# TT1-1-Top.net
KiCad netlist of a schematic drawn in Altium Designer
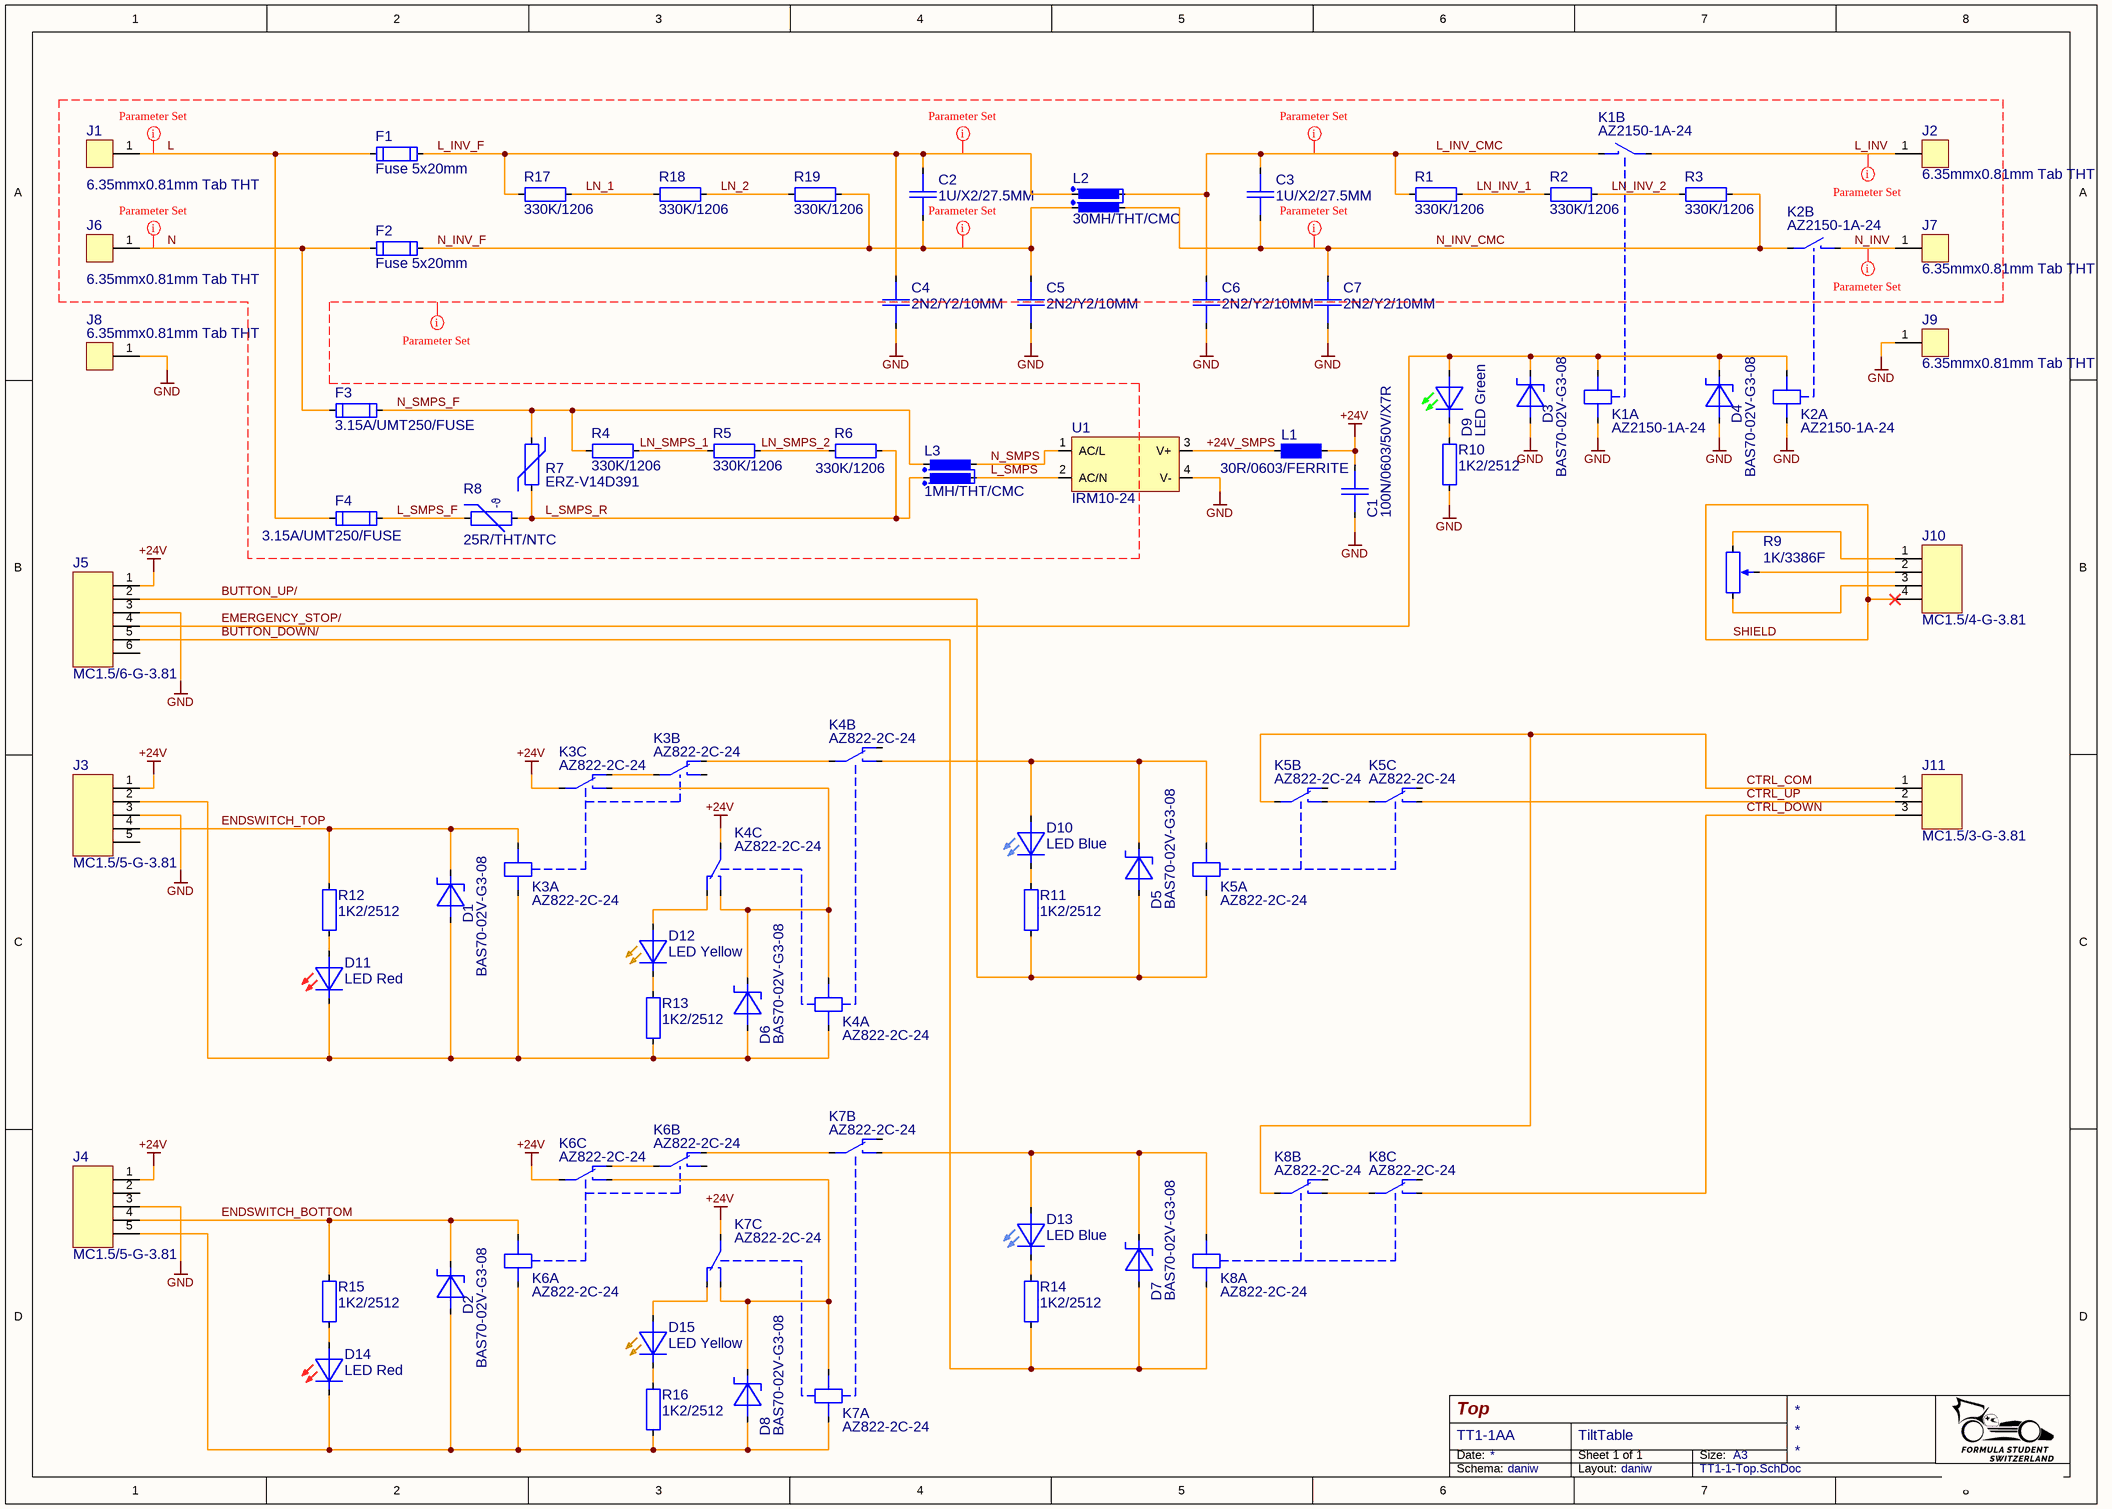
[diagram p0: TT1-1-Top.SchDoc]

(export (version "E")
  (design (tool "Eeschema 10.0.6"))
  (components
    (comp (ref "C1")
      (value "100N/0603/50V/X7R")
      (footprint "CAP0603_X7R")
      (description "CAP SM 0603 100nF 50V X7R")
      (fields (field (name "MANUFACTURER") "GENERIC"))
      (libsource (lib "daniw_altium_lib") (part "C"))
    )
    (comp (ref "C2")
      (value "1U/X2/27.5MM")
      (footprint "CAP2750P315X110X190-BL")
      (description "CAP THT 31.5X11X19 1uF 305V X2")
      (fields (field (name "MANUFACTURER") "GENERIC"))
      (libsource (lib "daniw_altium_lib") (part "C"))
    )
    (comp (ref "C3")
      (value "1U/X2/27.5MM")
      (footprint "CAP2750P315X110X190-BL")
      (description "CAP THT 31.5X11X19 1uF 305V X2")
      (fields (field (name "MANUFACTURER") "GENERIC"))
      (libsource (lib "daniw_altium_lib") (part "C"))
    )
    (comp (ref "C4")
      (value "2N2/Y2/10MM")
      (footprint "CAP1000P130X40X90-BL")
      (description "CAP THT 13X4X9 2.2nF 300V Y2")
      (fields (field (name "MANUFACTURER") "GENERIC"))
      (libsource (lib "daniw_altium_lib") (part "C"))
    )
    (comp (ref "C5")
      (value "2N2/Y2/10MM")
      (footprint "CAP1000P130X40X90-BL")
      (description "CAP THT 13X4X9 2.2nF 300V Y2")
      (fields (field (name "MANUFACTURER") "GENERIC"))
      (libsource (lib "daniw_altium_lib") (part "C"))
    )
    (comp (ref "C6")
      (value "2N2/Y2/10MM")
      (footprint "CAP1000P130X40X90-BL")
      (description "CAP THT 13X4X9 2.2nF 300V Y2")
      (fields (field (name "MANUFACTURER") "GENERIC"))
      (libsource (lib "daniw_altium_lib") (part "C"))
    )
    (comp (ref "C7")
      (value "2N2/Y2/10MM")
      (footprint "CAP1000P130X40X90-BL")
      (description "CAP THT 13X4X9 2.2nF 300V Y2")
      (fields (field (name "MANUFACTURER") "GENERIC"))
      (libsource (lib "daniw_altium_lib") (part "C"))
    )
    (comp (ref "D1")
      (value "BAS70-02V-G3-08")
      (footprint "SOD1608X065")
      (description "Small Signal Schottky Diode")
      (fields (field (name "MANUFACTURER") "Vishay"))
      (libsource (lib "daniw_altium_lib") (part "D_Schottky"))
    )
    (comp (ref "D2")
      (value "BAS70-02V-G3-08")
      (footprint "SOD1608X065")
      (description "Small Signal Schottky Diode")
      (fields (field (name "MANUFACTURER") "Vishay"))
      (libsource (lib "daniw_altium_lib") (part "D_Schottky"))
    )
    (comp (ref "D3")
      (value "BAS70-02V-G3-08")
      (footprint "SOD1608X065")
      (description "Small Signal Schottky Diode")
      (fields (field (name "MANUFACTURER") "Vishay"))
      (libsource (lib "daniw_altium_lib") (part "D_Schottky"))
    )
    (comp (ref "D4")
      (value "BAS70-02V-G3-08")
      (footprint "SOD1608X065")
      (description "Small Signal Schottky Diode")
      (fields (field (name "MANUFACTURER") "Vishay"))
      (libsource (lib "daniw_altium_lib") (part "D_Schottky"))
    )
    (comp (ref "D5")
      (value "BAS70-02V-G3-08")
      (footprint "SOD1608X065")
      (description "Small Signal Schottky Diode")
      (fields (field (name "MANUFACTURER") "Vishay"))
      (libsource (lib "daniw_altium_lib") (part "D_Schottky"))
    )
    (comp (ref "D6")
      (value "BAS70-02V-G3-08")
      (footprint "SOD1608X065")
      (description "Small Signal Schottky Diode")
      (fields (field (name "MANUFACTURER") "Vishay"))
      (libsource (lib "daniw_altium_lib") (part "D_Schottky"))
    )
    (comp (ref "D7")
      (value "BAS70-02V-G3-08")
      (footprint "SOD1608X065")
      (description "Small Signal Schottky Diode")
      (fields (field (name "MANUFACTURER") "Vishay"))
      (libsource (lib "daniw_altium_lib") (part "D_Schottky"))
    )
    (comp (ref "D8")
      (value "BAS70-02V-G3-08")
      (footprint "SOD1608X065")
      (description "Small Signal Schottky Diode")
      (fields (field (name "MANUFACTURER") "Vishay"))
      (libsource (lib "daniw_altium_lib") (part "D_Schottky"))
    )
    (comp (ref "D9")
      (value "LED Green")
      (footprint "LED0603_GREEN")
      (description "Generic LED Green 0603")
      (fields (field (name "PART NUMBER") "LED Green 0603") (field (name "MANUFACTURER") "GENERIC"))
      (libsource (lib "daniw_altium_lib") (part "LED_GREEN"))
    )
    (comp (ref "D10")
      (value "LED Blue")
      (footprint "LED0603_BLUE")
      (description "Generic LED Blue 0603")
      (fields (field (name "PART NUMBER") "LED Blue 0603") (field (name "MANUFACTURER") "GENERIC"))
      (libsource (lib "daniw_altium_lib") (part "LED_BLUE"))
    )
    (comp (ref "D11")
      (value "LED Red")
      (footprint "LED0603_RED")
      (description "Generic LED Red 0603")
      (fields (field (name "PART NUMBER") "LED Red 0603") (field (name "MANUFACTURER") "GENERIC"))
      (libsource (lib "daniw_altium_lib") (part "LED_RED"))
    )
    (comp (ref "D12")
      (value "LED Yellow")
      (footprint "LED0603_YELLOW")
      (description "Generic LED Yellow 0603")
      (fields (field (name "PART NUMBER") "LED Yellow 0603") (field (name "MANUFACTURER") "GENERIC"))
      (libsource (lib "daniw_altium_lib") (part "LED_YELLOW"))
    )
    (comp (ref "D13")
      (value "LED Blue")
      (footprint "LED0603_BLUE")
      (description "Generic LED Blue 0603")
      (fields (field (name "PART NUMBER") "LED Blue 0603") (field (name "MANUFACTURER") "GENERIC"))
      (libsource (lib "daniw_altium_lib") (part "LED_BLUE"))
    )
    (comp (ref "D14")
      (value "LED Red")
      (footprint "LED0603_RED")
      (description "Generic LED Red 0603")
      (fields (field (name "PART NUMBER") "LED Red 0603") (field (name "MANUFACTURER") "GENERIC"))
      (libsource (lib "daniw_altium_lib") (part "LED_RED"))
    )
    (comp (ref "D15")
      (value "LED Yellow")
      (footprint "LED0603_YELLOW")
      (description "Generic LED Yellow 0603")
      (fields (field (name "PART NUMBER") "LED Yellow 0603") (field (name "MANUFACTURER") "GENERIC"))
      (libsource (lib "daniw_altium_lib") (part "LED_YELLOW"))
    )
    (comp (ref "F1")
      (value "Fuse 5x20mm")
      (footprint "OGN_THR")
      (description "open fuse holder, 5 x 20 mm, THR, IEC 60335-1")
      (fields (field (name "PART NUMBER") "Fuse/5x20mm/OGN") (field (name "MANUFACTURER") "Schurter"))
      (libsource (lib "daniw_altium_lib") (part "Fuse"))
    )
    (comp (ref "F2")
      (value "Fuse 5x20mm")
      (footprint "OGN_THR")
      (description "open fuse holder, 5 x 20 mm, THR, IEC 60335-1")
      (fields (field (name "PART NUMBER") "Fuse/5x20mm/OGN") (field (name "MANUFACTURER") "Schurter"))
      (libsource (lib "daniw_altium_lib") (part "Fuse"))
    )
    (comp (ref "F3")
      (value "3.15A/UMT250/FUSE")
      (footprint "UMT250")
      (description "Fuse 250VAC 3.15A UMT250")
      (fields (field (name "MANUFACTURER") "Schurter"))
      (libsource (lib "daniw_altium_lib") (part "Fuse"))
    )
    (comp (ref "F4")
      (value "3.15A/UMT250/FUSE")
      (footprint "UMT250")
      (description "Fuse 250VAC 3.15A UMT250")
      (fields (field (name "MANUFACTURER") "Schurter"))
      (libsource (lib "daniw_altium_lib") (part "Fuse"))
    )
    (comp (ref "J1")
      (value "6.35mmx0.81mm Tab THT")
      (footprint "Tab_THT_635")
      (description "CONN QC TAB 0.250 SOLDER")
      (fields (field (name "PART NUMBER") "Tab_025_THT") (field (name "MANUFACTURER") "GENERIC"))
      (libsource (lib "") (part "CON1_1"))
    )
    (comp (ref "J2")
      (value "6.35mmx0.81mm Tab THT")
      (footprint "Tab_THT_635")
      (description "CONN QC TAB 0.250 SOLDER")
      (fields (field (name "PART NUMBER") "Tab_025_THT") (field (name "MANUFACTURER") "GENERIC"))
      (libsource (lib "daniw_altium_lib") (part "CON1"))
    )
    (comp (ref "J3")
      (value "MC1.5/5-G-3.81")
      (footprint "MC1.5/5-G-3.81")
      (description "Phoenix contact MC 1,5/ 5-G-3,81")
      (fields (field (name "MANUFACTURER") "Phoenix"))
      (libsource (lib "daniw_altium_lib") (part "CON5"))
    )
    (comp (ref "J4")
      (value "MC1.5/5-G-3.81")
      (footprint "MC1.5/5-G-3.81")
      (description "Phoenix contact MC 1,5/ 5-G-3,81")
      (fields (field (name "MANUFACTURER") "Phoenix"))
      (libsource (lib "daniw_altium_lib") (part "CON5"))
    )
    (comp (ref "J5")
      (value "MC1.5/6-G-3.81")
      (footprint "MC1.5/6-G-3.81")
      (description "Phoenix contact MC 1,5/ 6-G-3,81")
      (fields (field (name "MANUFACTURER") "Phoenix"))
      (libsource (lib "daniw_altium_lib") (part "CON6"))
    )
    (comp (ref "J6")
      (value "6.35mmx0.81mm Tab THT")
      (footprint "Tab_THT_635")
      (description "CONN QC TAB 0.250 SOLDER")
      (fields (field (name "PART NUMBER") "Tab_025_THT") (field (name "MANUFACTURER") "GENERIC"))
      (libsource (lib "") (part "CON1_1"))
    )
    (comp (ref "J7")
      (value "6.35mmx0.81mm Tab THT")
      (footprint "Tab_THT_635")
      (description "CONN QC TAB 0.250 SOLDER")
      (fields (field (name "PART NUMBER") "Tab_025_THT") (field (name "MANUFACTURER") "GENERIC"))
      (libsource (lib "daniw_altium_lib") (part "CON1"))
    )
    (comp (ref "J8")
      (value "6.35mmx0.81mm Tab THT")
      (footprint "Tab_THT_635")
      (description "CONN QC TAB 0.250 SOLDER")
      (fields (field (name "PART NUMBER") "Tab_025_THT") (field (name "MANUFACTURER") "GENERIC"))
      (libsource (lib "") (part "CON1_1"))
    )
    (comp (ref "J9")
      (value "6.35mmx0.81mm Tab THT")
      (footprint "Tab_THT_635")
      (description "CONN QC TAB 0.250 SOLDER")
      (fields (field (name "PART NUMBER") "Tab_025_THT") (field (name "MANUFACTURER") "GENERIC"))
      (libsource (lib "daniw_altium_lib") (part "CON1"))
    )
    (comp (ref "J10")
      (value "MC1.5/4-G-3.81")
      (footprint "MC1.5/4-G-3.81")
      (description "Phoenix contact MC 1,5/ 4-G-3,81")
      (fields (field (name "MANUFACTURER") "Phoenix"))
      (libsource (lib "daniw_altium_lib") (part "CON4"))
    )
    (comp (ref "J11")
      (value "MC1.5/3-G-3.81")
      (footprint "MC1.5/3-G-3.81")
      (description "Phoenix contact MC 1,5/ 3-G-3,81")
      (fields (field (name "MANUFACTURER") "Phoenix"))
      (libsource (lib "daniw_altium_lib") (part "CON3"))
    )
    (comp (ref "K1")
      (value "AZ2150-1A-24")
      (footprint "AZ2150-SPST-NO")
      (description "Miniature Power Relay, SPST-NO, 24V Coil, 40A 30VDC 300VAC")
      (fields (field (name "MANUFACTURER") "Zettler"))
      (libsource (lib "daniw_altium_lib") (part "REL_SPST_NO"))
    )
    (comp (ref "K2")
      (value "AZ2150-1A-24")
      (footprint "AZ2150-SPST-NO")
      (description "Miniature Power Relay, SPST-NO, 24V Coil, 40A 30VDC 300VAC")
      (fields (field (name "MANUFACTURER") "Zettler"))
      (libsource (lib "daniw_altium_lib") (part "REL_SPST_NO"))
    )
    (comp (ref "K3")
      (value "AZ822-2C-24")
      (footprint "AZ822")
      (description "Subminiature DIP Relay, DPDT, 24V 98mW Coil, 2A 220VDC 250VAC")
      (fields (field (name "MANUFACTURER") "Zettler"))
      (libsource (lib "daniw_altium_lib") (part "REL_DPDT"))
    )
    (comp (ref "K4")
      (value "AZ822-2C-24")
      (footprint "AZ822")
      (description "Subminiature DIP Relay, DPDT, 24V 98mW Coil, 2A 220VDC 250VAC")
      (fields (field (name "MANUFACTURER") "Zettler"))
      (libsource (lib "daniw_altium_lib") (part "REL_DPDT"))
    )
    (comp (ref "K5")
      (value "AZ822-2C-24")
      (footprint "AZ822")
      (description "Subminiature DIP Relay, DPDT, 24V 98mW Coil, 2A 220VDC 250VAC")
      (fields (field (name "MANUFACTURER") "Zettler"))
      (libsource (lib "daniw_altium_lib") (part "REL_DPDT"))
    )
    (comp (ref "K6")
      (value "AZ822-2C-24")
      (footprint "AZ822")
      (description "Subminiature DIP Relay, DPDT, 24V 98mW Coil, 2A 220VDC 250VAC")
      (fields (field (name "MANUFACTURER") "Zettler"))
      (libsource (lib "daniw_altium_lib") (part "REL_DPDT"))
    )
    (comp (ref "K7")
      (value "AZ822-2C-24")
      (footprint "AZ822")
      (description "Subminiature DIP Relay, DPDT, 24V 98mW Coil, 2A 220VDC 250VAC")
      (fields (field (name "MANUFACTURER") "Zettler"))
      (libsource (lib "daniw_altium_lib") (part "REL_DPDT"))
    )
    (comp (ref "K8")
      (value "AZ822-2C-24")
      (footprint "AZ822")
      (description "Subminiature DIP Relay, DPDT, 24V 98mW Coil, 2A 220VDC 250VAC")
      (fields (field (name "MANUFACTURER") "Zettler"))
      (libsource (lib "daniw_altium_lib") (part "REL_DPDT"))
    )
    (comp (ref "L1")
      (value "30R/0603/FERRITE")
      (footprint "FB0603")
      (description "30R@100MHz 5A 0603 Ferrite")
      (fields (field (name "MANUFACTURER") "GENERIC"))
      (libsource (lib "daniw_altium_lib") (part "Ferrite"))
    )
    (comp (ref "L2")
      (value "30MH/THT/CMC")
      (footprint "CMC-WE-CMBNC-XL-7448050530")
      (description "CMC 30mH 5A Würth CMBNC 7448050530")
      (fields (field (name "MANUFACTURER") "Würth"))
      (libsource (lib "daniw_altium_lib") (part "L_CMC_2"))
    )
    (comp (ref "L3")
      (value "1MH/THT/CMC")
      (footprint "DFKH-CASE-50-2")
      (description "CMC 1mH 2A THT Schurter DFKH-14-0003")
      (fields (field (name "MANUFACTURER") "SCHURTER"))
      (libsource (lib "") (part "L_CMC_2_1"))
    )
    (comp (ref "R1")
      (value "330K/1206")
      (footprint "R1206-0.80-WW")
      (description "RES SM 1206 330K")
      (fields (field (name "MANUFACTURER") "GENERIC"))
      (libsource (lib "daniw_altium_lib") (part "R"))
    )
    (comp (ref "R2")
      (value "330K/1206")
      (footprint "R1206-0.80-WW")
      (description "RES SM 1206 330K")
      (fields (field (name "MANUFACTURER") "GENERIC"))
      (libsource (lib "daniw_altium_lib") (part "R"))
    )
    (comp (ref "R3")
      (value "330K/1206")
      (footprint "R1206-0.80-WW")
      (description "RES SM 1206 330K")
      (fields (field (name "MANUFACTURER") "GENERIC"))
      (libsource (lib "daniw_altium_lib") (part "R"))
    )
    (comp (ref "R4")
      (value "330K/1206")
      (footprint "R1206-0.80-WW")
      (description "RES SM 1206 330K")
      (fields (field (name "MANUFACTURER") "GENERIC"))
      (libsource (lib "daniw_altium_lib") (part "R"))
    )
    (comp (ref "R5")
      (value "330K/1206")
      (footprint "R1206-0.80-WW")
      (description "RES SM 1206 330K")
      (fields (field (name "MANUFACTURER") "GENERIC"))
      (libsource (lib "daniw_altium_lib") (part "R"))
    )
    (comp (ref "R6")
      (value "330K/1206")
      (footprint "R1206-0.80-WW")
      (description "RES SM 1206 330K")
      (fields (field (name "MANUFACTURER") "GENERIC"))
      (libsource (lib "daniw_altium_lib") (part "R"))
    )
    (comp (ref "R7")
      (value "ERZ-V14D391")
      (footprint "RESD750W80D155")
      (description "VARISTOR 391V 6kA")
      (fields (field (name "MANUFACTURER") "GENERIC"))
      (libsource (lib "daniw_altium_lib") (part "R_VAR"))
    )
    (comp (ref "R8")
      (value "25R/THT/NTC")
      (footprint "RESD500W60D115")
      (description "RES NTC THT 5 25R")
      (fields (field (name "MANUFACTURER") "GENERIC"))
      (libsource (lib "daniw_altium_lib") (part "R_NTC"))
    )
    (comp (ref "R9")
      (value "1K/3386F")
      (footprint "3386F")
      (description "RES POT 3386F 1K")
      (fields (field (name "MANUFACTURER") "Bourns"))
      (libsource (lib "daniw_altium_lib") (part "R_POT"))
    )
    (comp (ref "R10")
      (value "1K2/2512")
      (footprint "R2512-0.65-WW")
      (description "RES SM 2512 1K2")
      (fields (field (name "MANUFACTURER") "GENERIC"))
      (libsource (lib "daniw_altium_lib") (part "R"))
    )
    (comp (ref "R11")
      (value "1K2/2512")
      (footprint "R2512-0.65-WW")
      (description "RES SM 2512 1K2")
      (fields (field (name "MANUFACTURER") "GENERIC"))
      (libsource (lib "daniw_altium_lib") (part "R"))
    )
    (comp (ref "R12")
      (value "1K2/2512")
      (footprint "R2512-0.65-WW")
      (description "RES SM 2512 1K2")
      (fields (field (name "MANUFACTURER") "GENERIC"))
      (libsource (lib "daniw_altium_lib") (part "R"))
    )
    (comp (ref "R13")
      (value "1K2/2512")
      (footprint "R2512-0.65-WW")
      (description "RES SM 2512 1K2")
      (fields (field (name "MANUFACTURER") "GENERIC"))
      (libsource (lib "daniw_altium_lib") (part "R"))
    )
    (comp (ref "R14")
      (value "1K2/2512")
      (footprint "R2512-0.65-WW")
      (description "RES SM 2512 1K2")
      (fields (field (name "MANUFACTURER") "GENERIC"))
      (libsource (lib "daniw_altium_lib") (part "R"))
    )
    (comp (ref "R15")
      (value "1K2/2512")
      (footprint "R2512-0.65-WW")
      (description "RES SM 2512 1K2")
      (fields (field (name "MANUFACTURER") "GENERIC"))
      (libsource (lib "daniw_altium_lib") (part "R"))
    )
    (comp (ref "R16")
      (value "1K2/2512")
      (footprint "R2512-0.65-WW")
      (description "RES SM 2512 1K2")
      (fields (field (name "MANUFACTURER") "GENERIC"))
      (libsource (lib "daniw_altium_lib") (part "R"))
    )
    (comp (ref "R17")
      (value "330K/1206")
      (footprint "R1206-0.80-WW")
      (description "RES SM 1206 330K")
      (fields (field (name "MANUFACTURER") "GENERIC"))
      (libsource (lib "daniw_altium_lib") (part "R"))
    )
    (comp (ref "R18")
      (value "330K/1206")
      (footprint "R1206-0.80-WW")
      (description "RES SM 1206 330K")
      (fields (field (name "MANUFACTURER") "GENERIC"))
      (libsource (lib "daniw_altium_lib") (part "R"))
    )
    (comp (ref "R19")
      (value "330K/1206")
      (footprint "R1206-0.80-WW")
      (description "RES SM 1206 330K")
      (fields (field (name "MANUFACTURER") "GENERIC"))
      (libsource (lib "daniw_altium_lib") (part "R"))
    )
    (comp (ref "U1")
      (value "IRM10-24")
      (footprint "IRM10")
      (description "10W AC-DC PCB-Mount Green Power Module, 24V")
      (libsource (lib "daniw_altium_lib") (part "IRM30"))
    )
  )
  (nets
    (net (code "1") (name "+24V") (class "Default")
      (node (ref "C1") (pin "1") (pinfunction "1_1") (pintype "passive"))
      (node (ref "J3") (pin "1") (pintype "passive"))
      (node (ref "J4") (pin "1") (pintype "passive"))
      (node (ref "J5") (pin "1") (pintype "passive"))
      (node (ref "K3") (pin "6") (pinfunction "COM2_6") (pintype "passive"))
      (node (ref "K4") (pin "6") (pinfunction "COM2_6") (pintype "passive"))
      (node (ref "K6") (pin "6") (pinfunction "COM2_6") (pintype "passive"))
      (node (ref "K7") (pin "6") (pinfunction "COM2_6") (pintype "passive"))
      (node (ref "L1") (pin "2") (pinfunction "2_2") (pintype "passive"))
    )
    (net (code "2") (name "/+24V_SMPS") (class "Default")
      (node (ref "L1") (pin "1") (pinfunction "1_1") (pintype "passive"))
      (node (ref "U1") (pin "3") (pinfunction "V+_3") (pintype "passive"))
    )
    (net (code "3") (name "/BUTTON_DOWN{slash}") (class "Default")
      (node (ref "D7") (pin "2") (pinfunction "2_2") (pintype "passive"))
      (node (ref "J5") (pin "5") (pintype "passive"))
      (node (ref "K8") (pin "2") (pinfunction "2_2") (pintype "passive"))
      (node (ref "R14") (pin "2") (pinfunction "2_2") (pintype "passive"))
    )
    (net (code "4") (name "/BUTTON_UP{slash}") (class "Default")
      (node (ref "D5") (pin "2") (pinfunction "2_2") (pintype "passive"))
      (node (ref "J5") (pin "2") (pintype "passive"))
      (node (ref "K5") (pin "1") (pinfunction "1_1") (pintype "passive"))
      (node (ref "R11") (pin "2") (pinfunction "2_2") (pintype "passive"))
    )
    (net (code "5") (name "/CTRL_COM") (class "Default")
      (node (ref "J11") (pin "1") (pintype "passive"))
      (node (ref "K5") (pin "3") (pinfunction "COM1_3") (pintype "passive"))
      (node (ref "K8") (pin "3") (pinfunction "COM1_3") (pintype "passive"))
    )
    (net (code "6") (name "/CTRL_DOWN") (class "Default")
      (node (ref "J11") (pin "3") (pintype "passive"))
      (node (ref "K8") (pin "8") (pinfunction "NO2_8") (pintype "passive"))
    )
    (net (code "7") (name "/CTRL_UP") (class "Default")
      (node (ref "J11") (pin "2") (pintype "passive"))
      (node (ref "K5") (pin "8") (pinfunction "NO2_8") (pintype "passive"))
    )
    (net (code "8") (name "/EMERGENCY_STOP{slash}") (class "Default")
      (node (ref "D3") (pin "1") (pinfunction "1_1") (pintype "passive"))
      (node (ref "D4") (pin "1") (pinfunction "1_1") (pintype "passive"))
      (node (ref "D9") (pin "2") (pinfunction "2_2") (pintype "passive"))
      (node (ref "J5") (pin "4") (pintype "passive"))
      (node (ref "K1") (pin "1") (pinfunction "1_1") (pintype "passive"))
      (node (ref "K2") (pin "1") (pinfunction "1_1") (pintype "passive"))
    )
    (net (code "9") (name "/ENDSWITCH_BOTTOM") (class "Default")
      (node (ref "D2") (pin "1") (pinfunction "1_1") (pintype "passive"))
      (node (ref "J4") (pin "4") (pintype "passive"))
      (node (ref "K6") (pin "1") (pinfunction "1_1") (pintype "passive"))
      (node (ref "R15") (pin "1") (pinfunction "1_1") (pintype "passive"))
    )
    (net (code "10") (name "/ENDSWITCH_TOP") (class "Default")
      (node (ref "D1") (pin "1") (pinfunction "1_1") (pintype "passive"))
      (node (ref "J3") (pin "4") (pintype "passive"))
      (node (ref "K3") (pin "1") (pinfunction "1_1") (pintype "passive"))
      (node (ref "R12") (pin "1") (pinfunction "1_1") (pintype "passive"))
    )
    (net (code "11") (name "/L") (class "Default")
      (node (ref "F1") (pin "1") (pinfunction "1_1") (pintype "passive"))
      (node (ref "F4") (pin "1") (pinfunction "1_1") (pintype "passive"))
      (node (ref "J1") (pin "1") (pintype "passive"))
    )
    (net (code "12") (name "/LN_1") (class "Default")
      (node (ref "R17") (pin "2") (pinfunction "2_2") (pintype "passive"))
      (node (ref "R18") (pin "1") (pinfunction "1_1") (pintype "passive"))
    )
    (net (code "13") (name "/LN_2") (class "Default")
      (node (ref "R18") (pin "2") (pinfunction "2_2") (pintype "passive"))
      (node (ref "R19") (pin "1") (pinfunction "1_1") (pintype "passive"))
    )
    (net (code "14") (name "/LN_INV_1") (class "Default")
      (node (ref "R1") (pin "2") (pinfunction "2_2") (pintype "passive"))
      (node (ref "R2") (pin "1") (pinfunction "1_1") (pintype "passive"))
    )
    (net (code "15") (name "/LN_INV_2") (class "Default")
      (node (ref "R2") (pin "2") (pinfunction "2_2") (pintype "passive"))
      (node (ref "R3") (pin "1") (pinfunction "1_1") (pintype "passive"))
    )
    (net (code "16") (name "/LN_SMPS_1") (class "Default")
      (node (ref "R4") (pin "2") (pinfunction "2_2") (pintype "passive"))
      (node (ref "R5") (pin "2") (pinfunction "2_2") (pintype "passive"))
    )
    (net (code "17") (name "/LN_SMPS_2") (class "Default")
      (node (ref "R5") (pin "1") (pinfunction "1_1") (pintype "passive"))
      (node (ref "R6") (pin "1") (pinfunction "1_1") (pintype "passive"))
    )
    (net (code "18") (name "/L_INV") (class "Default")
      (node (ref "J2") (pin "1") (pintype "passive"))
      (node (ref "K1") (pin "3") (pinfunction "COM1_3") (pintype "passive"))
    )
    (net (code "19") (name "/L_INV_CMC") (class "Default")
      (node (ref "C3") (pin "1") (pinfunction "1_1") (pintype "passive"))
      (node (ref "C6") (pin "1") (pinfunction "1_1") (pintype "passive"))
      (node (ref "K1") (pin "4") (pinfunction "NO1_4") (pintype "passive"))
      (node (ref "L2") (pin "4") (pinfunction "4_4") (pintype "passive"))
      (node (ref "R1") (pin "1") (pinfunction "1_1") (pintype "passive"))
    )
    (net (code "20") (name "/L_INV_F") (class "Default")
      (node (ref "C2") (pin "1") (pinfunction "1_1") (pintype "passive"))
      (node (ref "C4") (pin "1") (pinfunction "1_1") (pintype "passive"))
      (node (ref "F1") (pin "2") (pinfunction "2_2") (pintype "passive"))
      (node (ref "L2") (pin "2") (pinfunction "2_2") (pintype "passive"))
      (node (ref "R17") (pin "1") (pinfunction "1_1") (pintype "passive"))
    )
    (net (code "21") (name "/L_SMPS") (class "Default")
      (node (ref "L3") (pin "4") (pinfunction "4_4") (pintype "passive"))
      (node (ref "U1") (pin "2") (pinfunction "AC/N_2") (pintype "passive"))
    )
    (net (code "22") (name "/L_SMPS_F") (class "Default")
      (node (ref "F4") (pin "2") (pinfunction "2_2") (pintype "passive"))
      (node (ref "R8") (pin "1") (pinfunction "1_1") (pintype "passive"))
    )
    (net (code "23") (name "/L_SMPS_R") (class "Default")
      (node (ref "L3") (pin "2") (pinfunction "2_2") (pintype "passive"))
      (node (ref "R6") (pin "2") (pinfunction "2_2") (pintype "passive"))
      (node (ref "R7") (pin "2") (pinfunction "2_2") (pintype "passive"))
      (node (ref "R8") (pin "2") (pinfunction "2_2") (pintype "passive"))
    )
    (net (code "24") (name "/N") (class "Default")
      (node (ref "F2") (pin "1") (pinfunction "1_1") (pintype "passive"))
      (node (ref "F3") (pin "1") (pinfunction "1_1") (pintype "passive"))
      (node (ref "J6") (pin "1") (pintype "passive"))
    )
    (net (code "25") (name "/N_INV") (class "Default")
      (node (ref "J7") (pin "1") (pintype "passive"))
      (node (ref "K2") (pin "4") (pinfunction "NO1_4") (pintype "passive"))
    )
    (net (code "26") (name "/N_INV_CMC") (class "Default")
      (node (ref "C3") (pin "2") (pinfunction "2_2") (pintype "passive"))
      (node (ref "C7") (pin "1") (pinfunction "1_1") (pintype "passive"))
      (node (ref "K2") (pin "3") (pinfunction "COM1_3") (pintype "passive"))
      (node (ref "L2") (pin "3") (pinfunction "3_3") (pintype "passive"))
      (node (ref "R3") (pin "2") (pinfunction "2_2") (pintype "passive"))
    )
    (net (code "27") (name "/N_INV_F") (class "Default")
      (node (ref "C2") (pin "2") (pinfunction "2_2") (pintype "passive"))
      (node (ref "C5") (pin "1") (pinfunction "1_1") (pintype "passive"))
      (node (ref "F2") (pin "2") (pinfunction "2_2") (pintype "passive"))
      (node (ref "L2") (pin "1") (pinfunction "1_1") (pintype "passive"))
      (node (ref "R19") (pin "2") (pinfunction "2_2") (pintype "passive"))
    )
    (net (code "28") (name "/N_SMPS") (class "Default")
      (node (ref "L3") (pin "3") (pinfunction "3_3") (pintype "passive"))
      (node (ref "U1") (pin "1") (pinfunction "AC/L_1") (pintype "passive"))
    )
    (net (code "29") (name "/N_SMPS_F") (class "Default")
      (node (ref "F3") (pin "2") (pinfunction "2_2") (pintype "passive"))
      (node (ref "L3") (pin "1") (pinfunction "1_1") (pintype "passive"))
      (node (ref "R4") (pin "1") (pinfunction "1_1") (pintype "passive"))
      (node (ref "R7") (pin "1") (pinfunction "1_1") (pintype "passive"))
    )
    (net (code "30") (name "/SHIELD") (class "Default")
      (node (ref "J10") (pin "4") (pintype "passive+no_connect"))
    )
    (net (code "31") (name "GND") (class "Default")
      (node (ref "C1") (pin "2") (pinfunction "2_2") (pintype "passive"))
      (node (ref "C4") (pin "2") (pinfunction "2_2") (pintype "passive"))
      (node (ref "C5") (pin "2") (pinfunction "2_2") (pintype "passive"))
      (node (ref "C6") (pin "2") (pinfunction "2_2") (pintype "passive"))
      (node (ref "C7") (pin "2") (pinfunction "2_2") (pintype "passive"))
      (node (ref "D3") (pin "2") (pinfunction "2_2") (pintype "passive"))
      (node (ref "D4") (pin "2") (pinfunction "2_2") (pintype "passive"))
      (node (ref "J3") (pin "3") (pintype "passive"))
      (node (ref "J4") (pin "3") (pintype "passive"))
      (node (ref "J5") (pin "3") (pintype "passive"))
      (node (ref "J8") (pin "1") (pintype "passive"))
      (node (ref "J9") (pin "1") (pintype "passive"))
      (node (ref "K1") (pin "2") (pinfunction "2_2") (pintype "passive"))
      (node (ref "K2") (pin "2") (pinfunction "2_2") (pintype "passive"))
      (node (ref "R10") (pin "2") (pinfunction "2_2") (pintype "passive"))
      (node (ref "U1") (pin "4") (pinfunction "V-_4") (pintype "passive"))
    )
    (net (code "32") (name "Net-(D1-Pad2)") (class "Default")
      (node (ref "D1") (pin "2") (pinfunction "2_2") (pintype "passive"))
      (node (ref "D11") (pin "1") (pinfunction "1_1") (pintype "passive"))
      (node (ref "D6") (pin "2") (pinfunction "2_2") (pintype "passive"))
      (node (ref "J3") (pin "2") (pintype "passive"))
      (node (ref "K3") (pin "2") (pinfunction "2_2") (pintype "passive"))
      (node (ref "K4") (pin "2") (pinfunction "2_2") (pintype "passive"))
      (node (ref "R13") (pin "2") (pinfunction "2_2") (pintype "passive"))
    )
    (net (code "33") (name "Net-(D9-Pad1)") (class "Default")
      (node (ref "D9") (pin "1") (pinfunction "1_1") (pintype "passive"))
      (node (ref "R10") (pin "1") (pinfunction "1_1") (pintype "passive"))
    )
    (net (code "34") (name "Net-(D10-Pad1)") (class "Default")
      (node (ref "D10") (pin "1") (pinfunction "1_1") (pintype "passive"))
      (node (ref "R11") (pin "1") (pinfunction "1_1") (pintype "passive"))
    )
    (net (code "35") (name "Net-(D11-Pad2)") (class "Default")
      (node (ref "D11") (pin "2") (pinfunction "2_2") (pintype "passive"))
      (node (ref "R12") (pin "2") (pinfunction "2_2") (pintype "passive"))
    )
    (net (code "36") (name "Net-(D12-Pad1)") (class "Default")
      (node (ref "D12") (pin "1") (pinfunction "1_1") (pintype "passive"))
      (node (ref "R13") (pin "1") (pinfunction "1_1") (pintype "passive"))
    )
    (net (code "37") (name "Net-(D13-Pad1)") (class "Default")
      (node (ref "D13") (pin "1") (pinfunction "1_1") (pintype "passive"))
      (node (ref "R14") (pin "1") (pinfunction "1_1") (pintype "passive"))
    )
    (net (code "38") (name "Net-(D14-Pad1)") (class "Default")
      (node (ref "D14") (pin "1") (pinfunction "1_1") (pintype "passive"))
      (node (ref "D2") (pin "2") (pinfunction "2_2") (pintype "passive"))
      (node (ref "D8") (pin "2") (pinfunction "2_2") (pintype "passive"))
      (node (ref "J4") (pin "5") (pintype "passive"))
      (node (ref "K6") (pin "2") (pinfunction "2_2") (pintype "passive"))
      (node (ref "K7") (pin "2") (pinfunction "2_2") (pintype "passive"))
      (node (ref "R16") (pin "2") (pinfunction "2_2") (pintype "passive"))
    )
    (net (code "39") (name "Net-(D14-Pad2)") (class "Default")
      (node (ref "D14") (pin "2") (pinfunction "2_2") (pintype "passive"))
      (node (ref "R15") (pin "2") (pinfunction "2_2") (pintype "passive"))
    )
    (net (code "40") (name "Net-(D15-Pad1)") (class "Default")
      (node (ref "D15") (pin "1") (pinfunction "1_1") (pintype "passive"))
      (node (ref "R16") (pin "1") (pinfunction "1_1") (pintype "passive"))
    )
    (net (code "41") (name "Net-(J10-Pad1)") (class "Default")
      (node (ref "J10") (pin "1") (pintype "passive"))
      (node (ref "R9") (pin "2") (pinfunction "2_2") (pintype "passive"))
    )
    (net (code "42") (name "Net-(J10-Pad2)") (class "Default")
      (node (ref "J10") (pin "2") (pintype "passive"))
      (node (ref "R9") (pin "3") (pinfunction "3_3") (pintype "passive"))
    )
    (net (code "43") (name "Net-(J10-Pad3)") (class "Default")
      (node (ref "J10") (pin "3") (pintype "passive"))
      (node (ref "R9") (pin "1") (pinfunction "1_1") (pintype "passive"))
    )
    (net (code "44") (name "Net-(K3B-COM1)") (class "Default")
      (node (ref "K3") (pin "3") (pinfunction "COM1_3") (pintype "passive"))
      (node (ref "K3") (pin "7") (pinfunction "NC2_7") (pintype "passive"))
    )
    (net (code "45") (name "Net-(K3B-NC1)") (class "Default")
      (node (ref "K3") (pin "4") (pinfunction "NC1_4") (pintype "passive"))
      (node (ref "K4") (pin "3") (pinfunction "COM1_3") (pintype "passive"))
    )
    (net (code "46") (name "Net-(K3C-NO2)") (class "Default")
      (node (ref "D6") (pin "1") (pinfunction "1_1") (pintype "passive"))
      (node (ref "K3") (pin "8") (pinfunction "NO2_8") (pintype "passive"))
      (node (ref "K4") (pin "1") (pinfunction "1_1") (pintype "passive"))
      (node (ref "K4") (pin "8") (pinfunction "NO2_8") (pintype "passive"))
    )
    (net (code "47") (name "Net-(K4B-NO1)") (class "Default")
      (node (ref "D10") (pin "2") (pinfunction "2_2") (pintype "passive"))
      (node (ref "D5") (pin "1") (pinfunction "1_1") (pintype "passive"))
      (node (ref "K4") (pin "5") (pinfunction "NO1_5") (pintype "passive"))
      (node (ref "K5") (pin "2") (pinfunction "2_2") (pintype "passive"))
    )
    (net (code "48") (name "Net-(K4C-NC2)") (class "Default")
      (node (ref "D12") (pin "2") (pinfunction "2_2") (pintype "passive"))
      (node (ref "K4") (pin "7") (pinfunction "NC2_7") (pintype "passive"))
    )
    (net (code "49") (name "Net-(K5B-NO1)") (class "Default")
      (node (ref "K5") (pin "5") (pinfunction "NO1_5") (pintype "passive"))
      (node (ref "K5") (pin "6") (pinfunction "COM2_6") (pintype "passive"))
    )
    (net (code "50") (name "Net-(K6B-COM1)") (class "Default")
      (node (ref "K6") (pin "3") (pinfunction "COM1_3") (pintype "passive"))
      (node (ref "K6") (pin "7") (pinfunction "NC2_7") (pintype "passive"))
    )
    (net (code "51") (name "Net-(K6B-NC1)") (class "Default")
      (node (ref "K6") (pin "4") (pinfunction "NC1_4") (pintype "passive"))
      (node (ref "K7") (pin "3") (pinfunction "COM1_3") (pintype "passive"))
    )
    (net (code "52") (name "Net-(K6C-NO2)") (class "Default")
      (node (ref "D8") (pin "1") (pinfunction "1_1") (pintype "passive"))
      (node (ref "K6") (pin "8") (pinfunction "NO2_8") (pintype "passive"))
      (node (ref "K7") (pin "1") (pinfunction "1_1") (pintype "passive"))
      (node (ref "K7") (pin "8") (pinfunction "NO2_8") (pintype "passive"))
    )
    (net (code "53") (name "Net-(K7B-NO1)") (class "Default")
      (node (ref "D13") (pin "2") (pinfunction "2_2") (pintype "passive"))
      (node (ref "D7") (pin "1") (pinfunction "1_1") (pintype "passive"))
      (node (ref "K7") (pin "5") (pinfunction "NO1_5") (pintype "passive"))
      (node (ref "K8") (pin "1") (pinfunction "1_1") (pintype "passive"))
    )
    (net (code "54") (name "Net-(K7C-NC2)") (class "Default")
      (node (ref "D15") (pin "2") (pinfunction "2_2") (pintype "passive"))
      (node (ref "K7") (pin "7") (pinfunction "NC2_7") (pintype "passive"))
    )
    (net (code "55") (name "Net-(K8B-NO1)") (class "Default")
      (node (ref "K8") (pin "5") (pinfunction "NO1_5") (pintype "passive"))
      (node (ref "K8") (pin "6") (pinfunction "COM2_6") (pintype "passive"))
    )
    (net (code "56") (name "unconnected-(J3-Pad5)") (class "Default")
      (node (ref "J3") (pin "5") (pintype "passive"))
    )
    (net (code "57") (name "unconnected-(J4-Pad2)") (class "Default")
      (node (ref "J4") (pin "2") (pintype "passive"))
    )
    (net (code "58") (name "unconnected-(J5-Pad6)") (class "Default")
      (node (ref "J5") (pin "6") (pintype "passive"))
    )
    (net (code "59") (name "unconnected-(K3B-NO1-Pad5)") (class "Default")
      (node (ref "K3") (pin "5") (pinfunction "NO1_5") (pintype "passive"))
    )
    (net (code "60") (name "unconnected-(K4B-NC1-Pad4)") (class "Default")
      (node (ref "K4") (pin "4") (pinfunction "NC1_4") (pintype "passive"))
    )
    (net (code "61") (name "unconnected-(K5B-NC1-Pad4)") (class "Default")
      (node (ref "K5") (pin "4") (pinfunction "NC1_4") (pintype "passive"))
    )
    (net (code "62") (name "unconnected-(K5C-NC2-Pad7)") (class "Default")
      (node (ref "K5") (pin "7") (pinfunction "NC2_7") (pintype "passive"))
    )
    (net (code "63") (name "unconnected-(K6B-NO1-Pad5)") (class "Default")
      (node (ref "K6") (pin "5") (pinfunction "NO1_5") (pintype "passive"))
    )
    (net (code "64") (name "unconnected-(K7B-NC1-Pad4)") (class "Default")
      (node (ref "K7") (pin "4") (pinfunction "NC1_4") (pintype "passive"))
    )
    (net (code "65") (name "unconnected-(K8B-NC1-Pad4)") (class "Default")
      (node (ref "K8") (pin "4") (pinfunction "NC1_4") (pintype "passive"))
    )
    (net (code "66") (name "unconnected-(K8C-NC2-Pad7)") (class "Default")
      (node (ref "K8") (pin "7") (pinfunction "NC2_7") (pintype "passive"))
    )
  )
)
